# AST1015.net
KiCad netlist of a schematic drawn in EAGLE
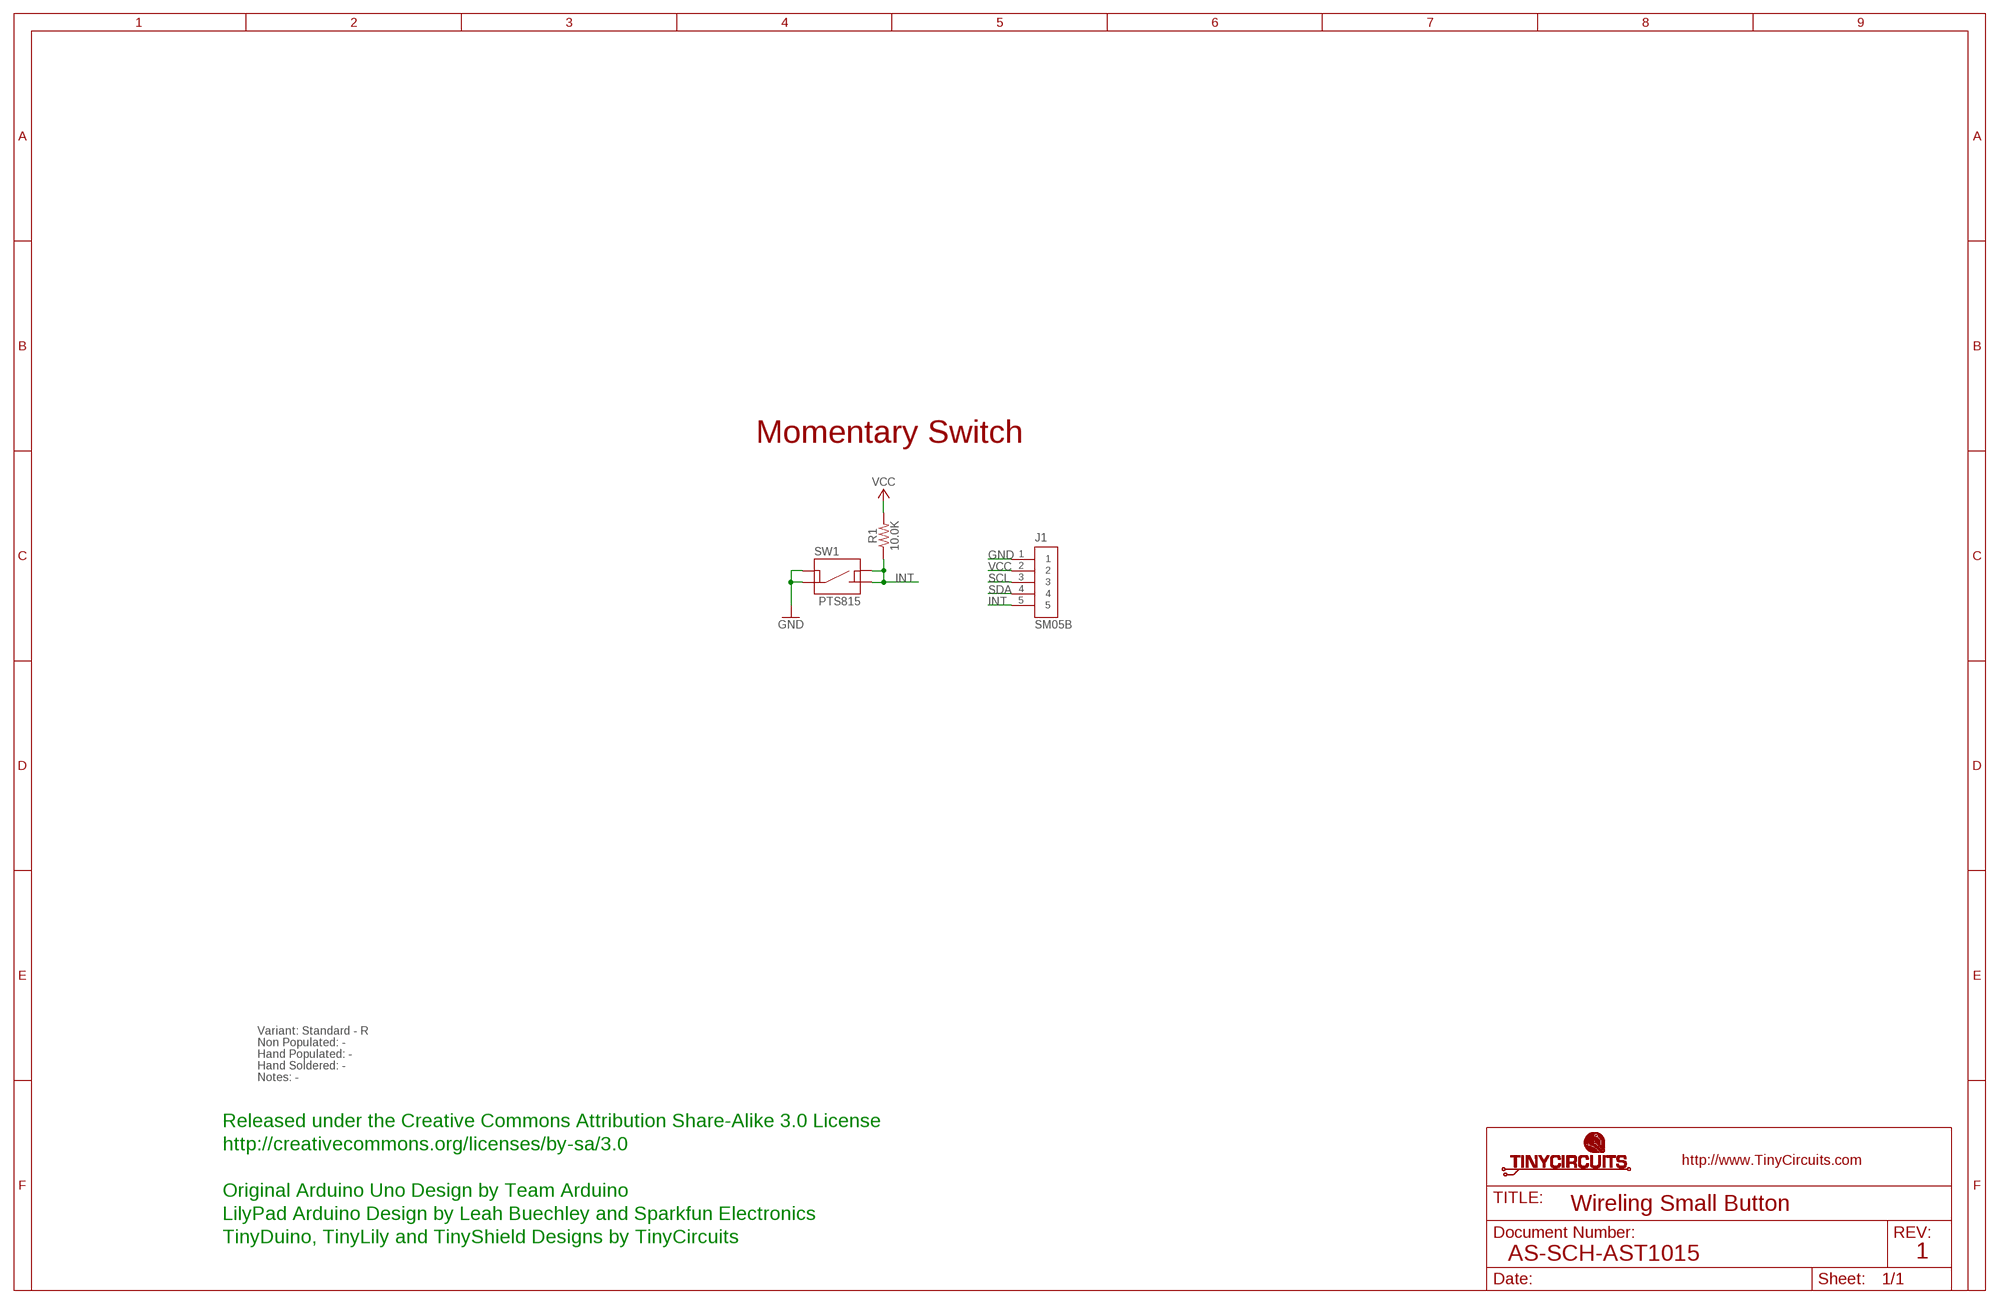
[diagram p0: schematic, sheet 1]

(export (version "E")
  (design (tool "Eeschema 10.0.6"))
  (components
    (comp (ref "J1")
      (value "SM05B")
      (footprint "eagle-import:JST_SH_5X1_EDGE")
      (fields (field (name "PARTNO") "AS-ITM-00340"))
      (libsource (lib "eagle-import") (part "AS-ITM-00340EDGE"))
    )
    (comp (ref "R1")
      (value "10.0K")
      (footprint "eagle-import:0402")
      (fields (field (name "PARTNO") "AS-ITM-00032"))
      (libsource (lib "eagle-import") (part "AS-ITM-00032"))
    )
    (comp (ref "SW1")
      (value "PTS815")
      (footprint "eagle-import:PTS815")
      (fields (field (name "PARTNO") "AS-ITM-00544"))
      (libsource (lib "eagle-import") (part "AS-ITM-00544"))
    )
  )
  (nets
    (net (code "1") (name "/INT") (class "Default")
      (node (ref "J1") (pin "5") (pinfunction "5_5") (pintype "bidirectional"))
      (node (ref "R1") (pin "1") (pinfunction "1_1") (pintype "passive"))
      (node (ref "SW1") (pin "3") (pinfunction "2_3") (pintype "bidirectional"))
      (node (ref "SW1") (pin "4") (pinfunction "4_4") (pintype "bidirectional"))
    )
    (net (code "2") (name "/SCL") (class "Default")
      (node (ref "J1") (pin "3") (pinfunction "3_3") (pintype "bidirectional"))
    )
    (net (code "3") (name "/SDA") (class "Default")
      (node (ref "J1") (pin "4") (pinfunction "4_4") (pintype "bidirectional"))
    )
    (net (code "4") (name "GND") (class "Default")
      (node (ref "J1") (pin "1") (pinfunction "1_1") (pintype "bidirectional"))
      (node (ref "SW1") (pin "1") (pinfunction "1_1") (pintype "bidirectional"))
      (node (ref "SW1") (pin "2") (pinfunction "3_2") (pintype "bidirectional"))
    )
    (net (code "5") (name "VCC") (class "Default")
      (node (ref "J1") (pin "2") (pinfunction "2_2") (pintype "bidirectional"))
      (node (ref "R1") (pin "2") (pinfunction "2_2") (pintype "passive"))
    )
  )
)
